# ControllerRC2.net
KiCad netlist of a schematic drawn in EAGLE
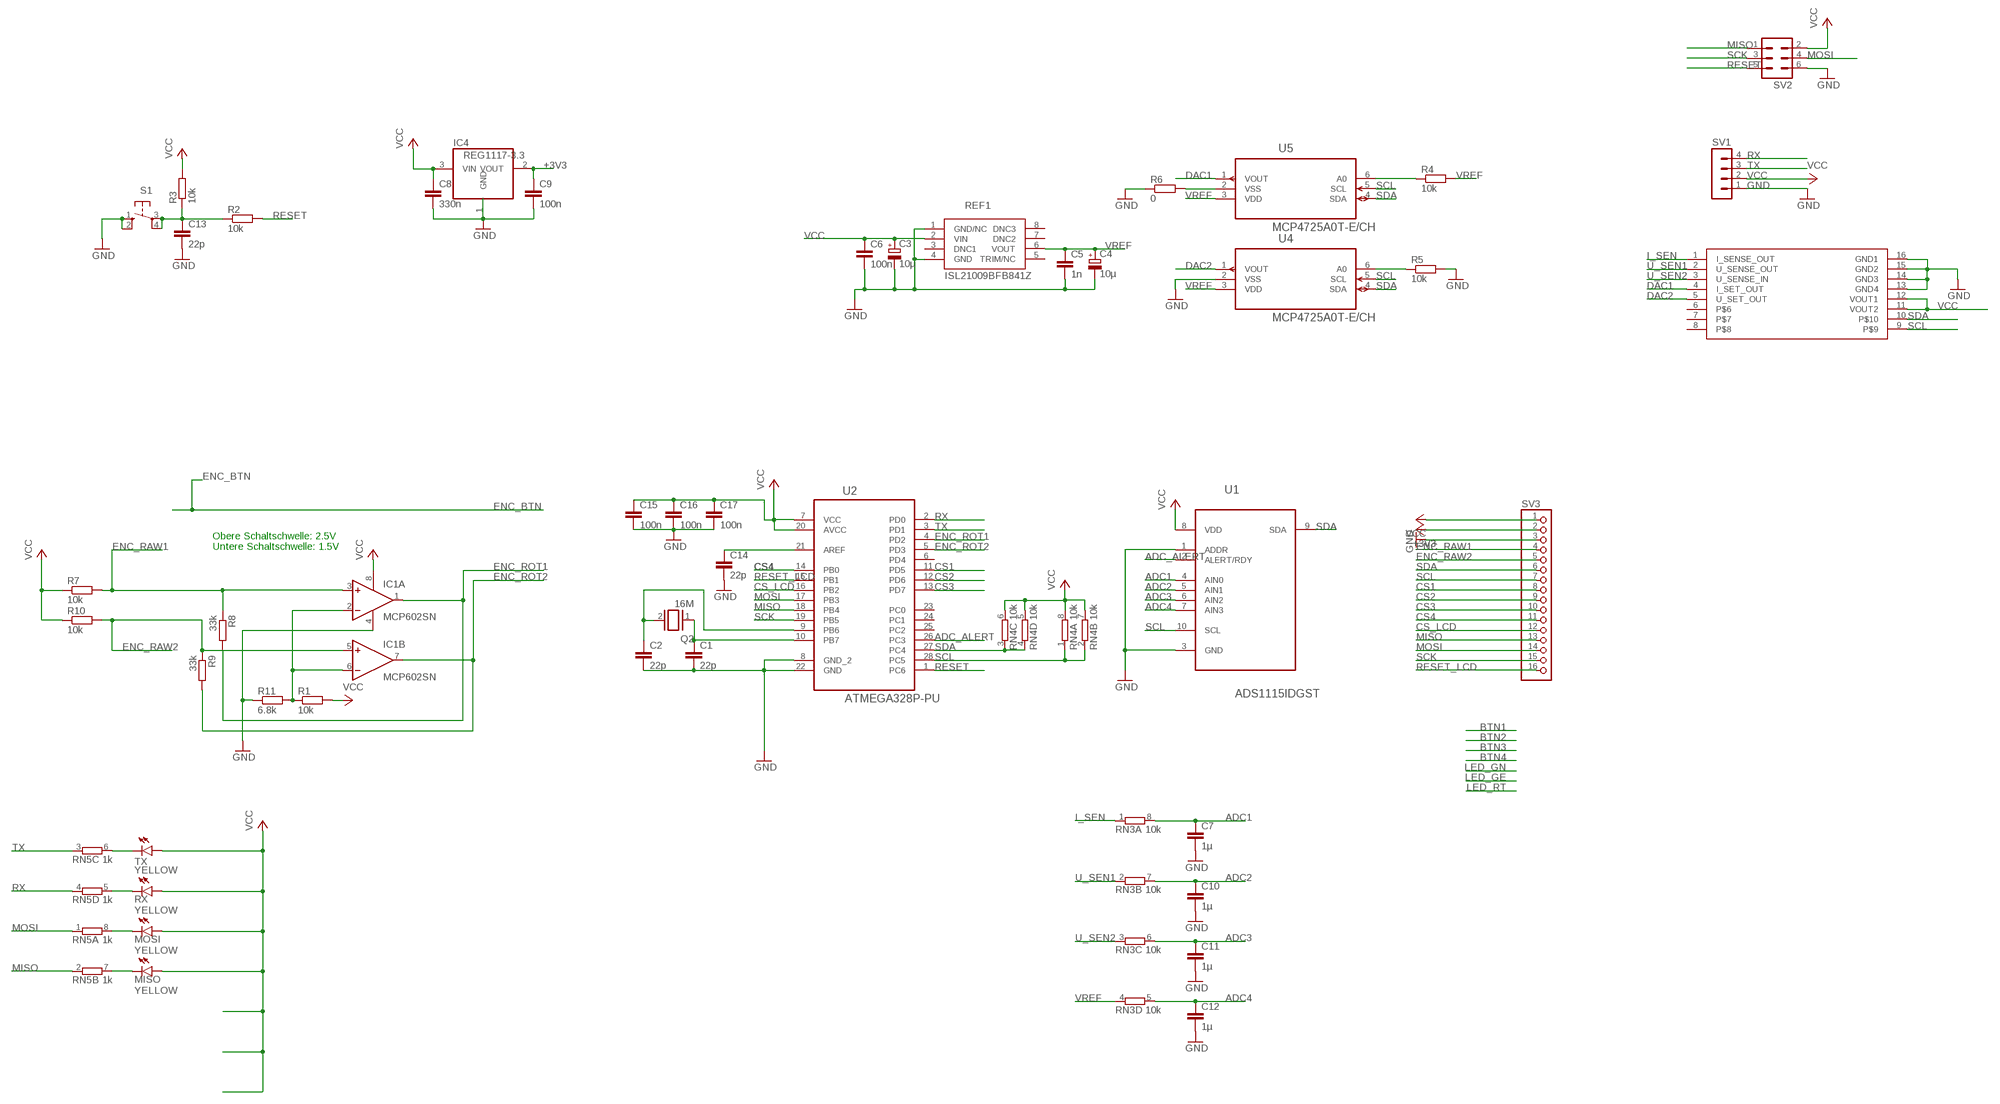
[diagram p0: schematic, sheet 1]

(export (version "E")
  (design (tool "Eeschema 10.0.6"))
  (components
    (comp (ref "C1")
      (value "22p")
      (footprint "eagle-import:C0603")
      (libsource (lib "eagle-import") (part "C-EUC0603"))
    )
    (comp (ref "C2")
      (value "22p")
      (footprint "eagle-import:C0603")
      (libsource (lib "eagle-import") (part "C-EUC0603"))
    )
    (comp (ref "C3")
      (value "10µ")
      (footprint "eagle-import:E2,5-6E")
      (libsource (lib "eagle-import") (part "CPOL-EUE2,5-6E"))
    )
    (comp (ref "C4")
      (value "10µ")
      (footprint "eagle-import:E2,5-6E")
      (libsource (lib "eagle-import") (part "CPOL-EUE2,5-6E"))
    )
    (comp (ref "C5")
      (value "1n")
      (footprint "eagle-import:C0603")
      (libsource (lib "eagle-import") (part "C-EUC0603"))
    )
    (comp (ref "C6")
      (value "100n")
      (footprint "eagle-import:C0603")
      (libsource (lib "eagle-import") (part "C-EUC0603"))
    )
    (comp (ref "C7")
      (value "1µ")
      (footprint "eagle-import:C0603")
      (libsource (lib "eagle-import") (part "C-EUC0603"))
    )
    (comp (ref "C8")
      (value "330n")
      (footprint "eagle-import:C0603")
      (libsource (lib "eagle-import") (part "C-EUC0603"))
    )
    (comp (ref "C9")
      (value "100n")
      (footprint "eagle-import:C0603")
      (libsource (lib "eagle-import") (part "C-EUC0603"))
    )
    (comp (ref "C10")
      (value "1µ")
      (footprint "eagle-import:C0603")
      (libsource (lib "eagle-import") (part "C-EUC0603"))
    )
    (comp (ref "C11")
      (value "1µ")
      (footprint "eagle-import:C0603")
      (libsource (lib "eagle-import") (part "C-EUC0603"))
    )
    (comp (ref "C12")
      (value "1µ")
      (footprint "eagle-import:C0603")
      (libsource (lib "eagle-import") (part "C-EUC0603"))
    )
    (comp (ref "C13")
      (value "22p")
      (footprint "eagle-import:C0603")
      (libsource (lib "eagle-import") (part "C-EUC0603"))
    )
    (comp (ref "C14")
      (value "22p")
      (footprint "eagle-import:C0603")
      (libsource (lib "eagle-import") (part "C-EUC0603"))
    )
    (comp (ref "C15")
      (value "100n")
      (footprint "eagle-import:C0603")
      (libsource (lib "eagle-import") (part "C-EUC0603"))
    )
    (comp (ref "C16")
      (value "100n")
      (footprint "eagle-import:C0603")
      (libsource (lib "eagle-import") (part "C-EUC0603"))
    )
    (comp (ref "C17")
      (value "100n")
      (footprint "eagle-import:C0603")
      (libsource (lib "eagle-import") (part "C-EUC0603"))
    )
    (comp (ref "IC1")
      (value "MCP602SN")
      (footprint "eagle-import:SO08")
      (libsource (lib "eagle-import") (part "MCP602SN"))
    )
    (comp (ref "IC4")
      (value "REG1117-3.3")
      (footprint "eagle-import:SOT223")
      (fields (field (name "MPN") "REG1117"))
      (libsource (lib "eagle-import") (part "REG1117"))
    )
    (comp (ref "MISO")
      (value "YELLOW")
      (footprint "eagle-import:CHIP-LED0805")
      (libsource (lib "eagle-import") (part "LEDCHIP-LED0805"))
    )
    (comp (ref "MOSI")
      (value "YELLOW")
      (footprint "eagle-import:CHIP-LED0805")
      (libsource (lib "eagle-import") (part "LEDCHIP-LED0805"))
    )
    (comp (ref "Q2")
      (value "16M")
      (footprint "eagle-import:QS")
      (libsource (lib "eagle-import") (part "XTAL/S"))
    )
    (comp (ref "R1")
      (value "10k")
      (footprint "eagle-import:R0603")
      (libsource (lib "eagle-import") (part "R-EU_R0603"))
    )
    (comp (ref "R2")
      (value "10k")
      (footprint "eagle-import:R0603")
      (libsource (lib "eagle-import") (part "R-EU_R0603"))
    )
    (comp (ref "R3")
      (value "10k")
      (footprint "eagle-import:R0603")
      (libsource (lib "eagle-import") (part "R-EU_R0603"))
    )
    (comp (ref "R4")
      (value "10k")
      (footprint "eagle-import:R0603")
      (libsource (lib "eagle-import") (part "R-EU_R0603"))
    )
    (comp (ref "R5")
      (value "10k")
      (footprint "eagle-import:R0603")
      (libsource (lib "eagle-import") (part "R-EU_R0603"))
    )
    (comp (ref "R6")
      (value "0")
      (footprint "eagle-import:R0603")
      (libsource (lib "eagle-import") (part "R-EU_R0603"))
    )
    (comp (ref "R7")
      (value "10k")
      (footprint "eagle-import:R0603")
      (libsource (lib "eagle-import") (part "R-EU_R0603"))
    )
    (comp (ref "R8")
      (value "33k")
      (footprint "eagle-import:R0603")
      (libsource (lib "eagle-import") (part "R-EU_R0603"))
    )
    (comp (ref "R9")
      (value "33k")
      (footprint "eagle-import:R0603")
      (libsource (lib "eagle-import") (part "R-EU_R0603"))
    )
    (comp (ref "R10")
      (value "10k")
      (footprint "eagle-import:R0603")
      (libsource (lib "eagle-import") (part "R-EU_R0603"))
    )
    (comp (ref "R11")
      (value "6.8k")
      (footprint "eagle-import:R0603")
      (libsource (lib "eagle-import") (part "R-EU_R0603"))
    )
    (comp (ref "REF1")
      (value "ISL21009BFB841Z")
      (footprint "eagle-import:SOIC127P600X175-8N")
      (libsource (lib "eagle-import") (part "ISL21009BFB841Z"))
    )
    (comp (ref "RN3")
      (value "10k")
      (footprint "eagle-import:0603-ARC")
      (libsource (lib "eagle-import") (part "4R-N0603-ARC"))
    )
    (comp (ref "RN4")
      (value "10k")
      (footprint "eagle-import:0603-ARC")
      (libsource (lib "eagle-import") (part "4R-N0603-ARC"))
    )
    (comp (ref "RN5")
      (value "1k")
      (footprint "eagle-import:0603-ARC")
      (libsource (lib "eagle-import") (part "4R-N0603-ARC"))
    )
    (comp (ref "RX")
      (value "YELLOW")
      (footprint "eagle-import:CHIP-LED0805")
      (libsource (lib "eagle-import") (part "LEDCHIP-LED0805"))
    )
    (comp (ref "S1")
      (value "10-XX")
      (footprint "eagle-import:B3F-10XX")
      (fields (field (name "MPN") "B3F-1000"))
      (libsource (lib "eagle-import") (part "10-XX"))
    )
    (comp (ref "SV1")
      (value "MA04-1")
      (footprint "eagle-import:MA04-1")
      (libsource (lib "eagle-import") (part "MA04-1"))
    )
    (comp (ref "SV2")
      (value "MA03-2")
      (footprint "eagle-import:MA03-2")
      (libsource (lib "eagle-import") (part "MA03-2"))
    )
    (comp (ref "SV3")
      (value "PINHD-1X16")
      (footprint "eagle-import:1X16")
      (libsource (lib "eagle-import") (part "PINHD-1X16"))
    )
    (comp (ref "TX")
      (value "YELLOW")
      (footprint "eagle-import:CHIP-LED0805")
      (libsource (lib "eagle-import") (part "LEDCHIP-LED0805"))
    )
    (comp (ref "U$1")
      (value "DCPINHEADER")
      (footprint "eagle-import:CDIP16")
      (libsource (lib "eagle-import") (part "DCPINHEADER"))
    )
    (comp (ref "U1")
      (value "ADS1115IDGST")
      (footprint "eagle-import:SOP50P490X110-10N")
      (libsource (lib "eagle-import") (part "ADS1115IDGST"))
    )
    (comp (ref "U2")
      (value "ATMEGA328P-PU")
      (footprint "eagle-import:DIP254P762X457-28")
      (libsource (lib "eagle-import") (part "ATMEGA328P-PU"))
    )
    (comp (ref "U4")
      (value "MCP4725A0T-E/CH")
      (footprint "eagle-import:SOT95P270X145-6N")
      (libsource (lib "eagle-import") (part "MCP4725A0T-E/CH"))
    )
    (comp (ref "U5")
      (value "MCP4725A0T-E/CH")
      (footprint "eagle-import:SOT95P270X145-6N")
      (libsource (lib "eagle-import") (part "MCP4725A0T-E/CH"))
    )
  )
  (nets
    (net (code "1") (name "+3V3") (class "Default")
      (node (ref "C9") (pin "1") (pinfunction "1_1") (pintype "passive"))
      (node (ref "IC4") (pin "2") (pinfunction "VOUT_2") (pintype "output"))
      (node (ref "SV3") (pin "2") (pinfunction "2_2") (pintype "passive"))
    )
    (net (code "2") (name "/ADC1") (class "Default")
      (node (ref "C7") (pin "1") (pinfunction "1_1") (pintype "passive"))
      (node (ref "RN3") (pin "8") (pinfunction "2_8") (pintype "passive"))
      (node (ref "U1") (pin "4") (pinfunction "AIN0_4") (pintype "input"))
    )
    (net (code "3") (name "/ADC2") (class "Default")
      (node (ref "C10") (pin "1") (pinfunction "1_1") (pintype "passive"))
      (node (ref "RN3") (pin "7") (pinfunction "2_7") (pintype "passive"))
      (node (ref "U1") (pin "5") (pinfunction "AIN1_5") (pintype "input"))
    )
    (net (code "4") (name "/ADC3") (class "Default")
      (node (ref "C11") (pin "1") (pinfunction "1_1") (pintype "passive"))
      (node (ref "RN3") (pin "6") (pinfunction "2_6") (pintype "passive"))
      (node (ref "U1") (pin "6") (pinfunction "AIN2_6") (pintype "input"))
    )
    (net (code "5") (name "/ADC4") (class "Default")
      (node (ref "C12") (pin "1") (pinfunction "1_1") (pintype "passive"))
      (node (ref "RN3") (pin "5") (pinfunction "2_5") (pintype "passive"))
      (node (ref "U1") (pin "7") (pinfunction "AIN3_7") (pintype "input"))
    )
    (net (code "6") (name "/ADC_ALERT") (class "Default")
      (node (ref "U1") (pin "2") (pinfunction "ALERT/RDY_2") (pintype "input"))
      (node (ref "U2") (pin "26") (pinfunction "PC3_26") (pintype "bidirectional"))
    )
    (net (code "11") (name "/CS1") (class "Default")
      (node (ref "SV3") (pin "8") (pinfunction "8_8") (pintype "passive"))
      (node (ref "U2") (pin "11") (pinfunction "PD5_11") (pintype "bidirectional"))
    )
    (net (code "12") (name "/CS2") (class "Default")
      (node (ref "SV3") (pin "9") (pinfunction "9_9") (pintype "passive"))
      (node (ref "U2") (pin "12") (pinfunction "PD6_12") (pintype "bidirectional"))
    )
    (net (code "13") (name "/CS3") (class "Default")
      (node (ref "SV3") (pin "10") (pinfunction "10_10") (pintype "passive"))
      (node (ref "U2") (pin "13") (pinfunction "PD7_13") (pintype "bidirectional"))
    )
    (net (code "14") (name "/CS4") (class "Default")
      (node (ref "SV3") (pin "11") (pinfunction "11_11") (pintype "passive"))
      (node (ref "U2") (pin "14") (pinfunction "PB0_14") (pintype "bidirectional"))
    )
    (net (code "15") (name "/CS_LCD") (class "Default")
      (node (ref "SV3") (pin "12") (pinfunction "12_12") (pintype "passive"))
      (node (ref "U2") (pin "16") (pinfunction "PB2_16") (pintype "bidirectional"))
    )
    (net (code "16") (name "/DAC1") (class "Default")
      (node (ref "U$1") (pin "4") (pinfunction "I_SET_OUT_4") (pintype "bidirectional"))
      (node (ref "U5") (pin "1") (pinfunction "VOUT_1") (pintype "output"))
    )
    (net (code "17") (name "/DAC2") (class "Default")
      (node (ref "U$1") (pin "5") (pinfunction "U_SET_OUT_5") (pintype "bidirectional"))
      (node (ref "U4") (pin "1") (pinfunction "VOUT_1") (pintype "output"))
    )
    (net (code "19") (name "/ENC_RAW1") (class "Default")
      (node (ref "IC1") (pin "3") (pinfunction "+IN_3") (pintype "input"))
      (node (ref "R7") (pin "2") (pinfunction "2_2") (pintype "passive"))
      (node (ref "R8") (pin "1") (pinfunction "1_1") (pintype "passive"))
      (node (ref "SV3") (pin "4") (pinfunction "4_4") (pintype "passive"))
    )
    (net (code "20") (name "/ENC_RAW2") (class "Default")
      (node (ref "IC1") (pin "5") (pinfunction "+IN_5") (pintype "input"))
      (node (ref "R10") (pin "2") (pinfunction "2_2") (pintype "passive"))
      (node (ref "R9") (pin "1") (pinfunction "1_1") (pintype "passive"))
      (node (ref "SV3") (pin "5") (pinfunction "5_5") (pintype "passive"))
    )
    (net (code "21") (name "/ENC_ROT1") (class "Default")
      (node (ref "IC1") (pin "1") (pinfunction "OUT_1") (pintype "output"))
      (node (ref "R8") (pin "2") (pinfunction "2_2") (pintype "passive"))
      (node (ref "U2") (pin "4") (pinfunction "PD2_4") (pintype "bidirectional"))
    )
    (net (code "22") (name "/ENC_ROT2") (class "Default")
      (node (ref "IC1") (pin "7") (pinfunction "OUT_7") (pintype "output"))
      (node (ref "R9") (pin "2") (pinfunction "2_2") (pintype "passive"))
      (node (ref "U2") (pin "5") (pinfunction "PD3_5") (pintype "bidirectional"))
    )
    (net (code "23") (name "/I_SEN") (class "Default")
      (node (ref "RN3") (pin "1") (pinfunction "1_1") (pintype "passive"))
      (node (ref "U$1") (pin "1") (pinfunction "I_SENSE_OUT_1") (pintype "bidirectional"))
    )
    (net (code "27") (name "/MISO") (class "Default")
      (node (ref "RN5") (pin "2") (pinfunction "1_2") (pintype "passive"))
      (node (ref "SV2") (pin "1") (pinfunction "1_1") (pintype "passive"))
      (node (ref "SV3") (pin "13") (pinfunction "13_13") (pintype "passive"))
      (node (ref "U2") (pin "18") (pinfunction "PB4_18") (pintype "bidirectional"))
    )
    (net (code "28") (name "/MOSI") (class "Default")
      (node (ref "RN5") (pin "1") (pinfunction "1_1") (pintype "passive"))
      (node (ref "SV2") (pin "4") (pinfunction "4_4") (pintype "passive"))
      (node (ref "SV3") (pin "14") (pinfunction "14_14") (pintype "passive"))
      (node (ref "U2") (pin "17") (pinfunction "PB3_17") (pintype "bidirectional"))
    )
    (net (code "29") (name "/RESET") (class "Default")
      (node (ref "R2") (pin "2") (pinfunction "2_2") (pintype "passive"))
      (node (ref "SV2") (pin "5") (pinfunction "5_5") (pintype "passive"))
      (node (ref "U2") (pin "1") (pinfunction "PC6_1") (pintype "bidirectional"))
    )
    (net (code "30") (name "/RESET_LCD") (class "Default")
      (node (ref "SV3") (pin "16") (pinfunction "16_16") (pintype "passive"))
      (node (ref "U2") (pin "15") (pinfunction "PB1_15") (pintype "bidirectional"))
    )
    (net (code "31") (name "/RX") (class "Default")
      (node (ref "RN5") (pin "4") (pinfunction "1_4") (pintype "passive"))
      (node (ref "SV1") (pin "4") (pinfunction "4_4") (pintype "passive"))
      (node (ref "U2") (pin "2") (pinfunction "PD0_2") (pintype "bidirectional"))
    )
    (net (code "32") (name "/SCK") (class "Default")
      (node (ref "SV2") (pin "3") (pinfunction "3_3") (pintype "passive"))
      (node (ref "SV3") (pin "15") (pinfunction "15_15") (pintype "passive"))
      (node (ref "U2") (pin "19") (pinfunction "PB5_19") (pintype "bidirectional"))
    )
    (net (code "33") (name "/SCL") (class "Default")
      (node (ref "RN4") (pin "1") (pinfunction "1_1") (pintype "passive"))
      (node (ref "RN4") (pin "2") (pinfunction "1_2") (pintype "passive"))
      (node (ref "SV3") (pin "7") (pinfunction "7_7") (pintype "passive"))
      (node (ref "U$1") (pin "9") (pinfunction "P$9_9") (pintype "bidirectional"))
      (node (ref "U1") (pin "10") (pinfunction "SCL_10") (pintype "input"))
      (node (ref "U2") (pin "28") (pinfunction "PC5_28") (pintype "bidirectional"))
      (node (ref "U4") (pin "5") (pinfunction "SCL_5") (pintype "input"))
      (node (ref "U5") (pin "5") (pinfunction "SCL_5") (pintype "input"))
    )
    (net (code "34") (name "/SDA") (class "Default")
      (node (ref "RN4") (pin "3") (pinfunction "1_3") (pintype "passive"))
      (node (ref "RN4") (pin "4") (pinfunction "1_4") (pintype "passive"))
      (node (ref "SV3") (pin "6") (pinfunction "6_6") (pintype "passive"))
      (node (ref "U$1") (pin "10") (pinfunction "P$10_10") (pintype "bidirectional"))
      (node (ref "U1") (pin "9") (pinfunction "SDA_9") (pintype "bidirectional"))
      (node (ref "U2") (pin "27") (pinfunction "PC4_27") (pintype "bidirectional"))
      (node (ref "U4") (pin "4") (pinfunction "SDA_4") (pintype "bidirectional"))
      (node (ref "U5") (pin "4") (pinfunction "SDA_4") (pintype "bidirectional"))
    )
    (net (code "35") (name "/TX") (class "Default")
      (node (ref "RN5") (pin "3") (pinfunction "1_3") (pintype "passive"))
      (node (ref "SV1") (pin "3") (pinfunction "3_3") (pintype "passive"))
      (node (ref "U2") (pin "3") (pinfunction "PD1_3") (pintype "bidirectional"))
    )
    (net (code "36") (name "/U_SEN1") (class "Default")
      (node (ref "RN3") (pin "2") (pinfunction "1_2") (pintype "passive"))
      (node (ref "U$1") (pin "2") (pinfunction "U_SENSE_OUT_2") (pintype "bidirectional"))
    )
    (net (code "37") (name "/U_SEN2") (class "Default")
      (node (ref "RN3") (pin "3") (pinfunction "1_3") (pintype "passive"))
      (node (ref "U$1") (pin "3") (pinfunction "U_SENSE_IN_3") (pintype "bidirectional"))
    )
    (net (code "38") (name "/VREF") (class "Default")
      (node (ref "C4") (pin "+") (pinfunction "+_+") (pintype "passive"))
      (node (ref "C5") (pin "1") (pinfunction "1_1") (pintype "passive"))
      (node (ref "R4") (pin "2") (pinfunction "2_2") (pintype "passive"))
      (node (ref "REF1") (pin "6") (pinfunction "VOUT_6") (pintype "bidirectional"))
      (node (ref "RN3") (pin "4") (pinfunction "1_4") (pintype "passive"))
      (node (ref "U4") (pin "3") (pinfunction "VDD_3") (pintype "power_in"))
      (node (ref "U5") (pin "3") (pinfunction "VDD_3") (pintype "power_in"))
    )
    (net (code "39") (name "GND") (class "Default")
      (node (ref "C1") (pin "2") (pinfunction "2_2") (pintype "passive"))
      (node (ref "C10") (pin "2") (pinfunction "2_2") (pintype "passive"))
      (node (ref "C11") (pin "2") (pinfunction "2_2") (pintype "passive"))
      (node (ref "C12") (pin "2") (pinfunction "2_2") (pintype "passive"))
      (node (ref "C13") (pin "2") (pinfunction "2_2") (pintype "passive"))
      (node (ref "C14") (pin "2") (pinfunction "2_2") (pintype "passive"))
      (node (ref "C15") (pin "2") (pinfunction "2_2") (pintype "passive"))
      (node (ref "C16") (pin "2") (pinfunction "2_2") (pintype "passive"))
      (node (ref "C17") (pin "2") (pinfunction "2_2") (pintype "passive"))
      (node (ref "C2") (pin "2") (pinfunction "2_2") (pintype "passive"))
      (node (ref "C3") (pin "-") (pinfunction "-_-") (pintype "passive"))
      (node (ref "C4") (pin "-") (pinfunction "-_-") (pintype "passive"))
      (node (ref "C5") (pin "2") (pinfunction "2_2") (pintype "passive"))
      (node (ref "C6") (pin "2") (pinfunction "2_2") (pintype "passive"))
      (node (ref "C7") (pin "2") (pinfunction "2_2") (pintype "passive"))
      (node (ref "C8") (pin "2") (pinfunction "2_2") (pintype "passive"))
      (node (ref "C9") (pin "2") (pinfunction "2_2") (pintype "passive"))
      (node (ref "IC1") (pin "4") (pinfunction "V-_4") (pintype "power_in"))
      (node (ref "IC4") (pin "1") (pinfunction "GND_1") (pintype "power_in"))
      (node (ref "R11") (pin "1") (pinfunction "1_1") (pintype "passive"))
      (node (ref "R5") (pin "2") (pinfunction "2_2") (pintype "passive"))
      (node (ref "R6") (pin "1") (pinfunction "1_1") (pintype "passive"))
      (node (ref "REF1") (pin "1") (pinfunction "GND/NC_1") (pintype "bidirectional"))
      (node (ref "REF1") (pin "4") (pinfunction "GND_4") (pintype "bidirectional"))
      (node (ref "S1") (pin "1") (pinfunction "S_1") (pintype "passive"))
      (node (ref "S1") (pin "2") (pinfunction "S1_2") (pintype "passive"))
      (node (ref "SV1") (pin "1") (pinfunction "1_1") (pintype "passive"))
      (node (ref "SV2") (pin "6") (pinfunction "6_6") (pintype "passive"))
      (node (ref "SV3") (pin "3") (pinfunction "3_3") (pintype "passive"))
      (node (ref "U$1") (pin "13") (pinfunction "GND4_13") (pintype "bidirectional"))
      (node (ref "U$1") (pin "14") (pinfunction "GND3_14") (pintype "bidirectional"))
      (node (ref "U$1") (pin "15") (pinfunction "GND2_15") (pintype "bidirectional"))
      (node (ref "U$1") (pin "16") (pinfunction "GND1_16") (pintype "bidirectional"))
      (node (ref "U1") (pin "1") (pinfunction "ADDR_1") (pintype "input"))
      (node (ref "U1") (pin "3") (pinfunction "GND_3") (pintype "passive"))
      (node (ref "U2") (pin "22") (pinfunction "GND_22") (pintype "passive"))
      (node (ref "U2") (pin "8") (pinfunction "GND_2_8") (pintype "passive"))
      (node (ref "U4") (pin "2") (pinfunction "VSS_2") (pintype "power_in"))
    )
    (net (code "40") (name "Net-(IC1A--IN)") (class "Default")
      (node (ref "IC1") (pin "2") (pinfunction "-IN_2") (pintype "input"))
      (node (ref "IC1") (pin "6") (pinfunction "-IN_6") (pintype "input"))
      (node (ref "R1") (pin "1") (pinfunction "1_1") (pintype "passive"))
      (node (ref "R11") (pin "2") (pinfunction "2_2") (pintype "passive"))
    )
    (net (code "41") (name "Net-(RN5A-2)") (class "Default")
      (node (ref "MOSI") (pin "C") (pinfunction "C_C") (pintype "passive"))
      (node (ref "RN5") (pin "8") (pinfunction "2_8") (pintype "passive"))
    )
    (net (code "42") (name "Net-(RN5B-2)") (class "Default")
      (node (ref "MISO") (pin "C") (pinfunction "C_C") (pintype "passive"))
      (node (ref "RN5") (pin "7") (pinfunction "2_7") (pintype "passive"))
    )
    (net (code "43") (name "Net-(RN5C-2)") (class "Default")
      (node (ref "RN5") (pin "6") (pinfunction "2_6") (pintype "passive"))
      (node (ref "TX") (pin "C") (pinfunction "C_C") (pintype "passive"))
    )
    (net (code "44") (name "Net-(RN5D-2)") (class "Default")
      (node (ref "RN5") (pin "5") (pinfunction "2_5") (pintype "passive"))
      (node (ref "RX") (pin "C") (pinfunction "C_C") (pintype "passive"))
    )
    (net (code "45") (name "Net-(S1-P)") (class "Default")
      (node (ref "C13") (pin "1") (pinfunction "1_1") (pintype "passive"))
      (node (ref "R2") (pin "1") (pinfunction "1_1") (pintype "passive"))
      (node (ref "R3") (pin "1") (pinfunction "1_1") (pintype "passive"))
      (node (ref "S1") (pin "3") (pinfunction "P_3") (pintype "passive"))
      (node (ref "S1") (pin "4") (pinfunction "P1_4") (pintype "passive"))
    )
    (net (code "46") (name "Net-(U2-AREF)") (class "Default")
      (node (ref "C14") (pin "1") (pinfunction "1_1") (pintype "passive"))
      (node (ref "U2") (pin "21") (pinfunction "AREF_21") (pintype "input"))
    )
    (net (code "47") (name "Net-(U2-PB6)") (class "Default")
      (node (ref "C2") (pin "1") (pinfunction "1_1") (pintype "passive"))
      (node (ref "Q2") (pin "2") (pinfunction "2_2") (pintype "passive"))
      (node (ref "U2") (pin "9") (pinfunction "PB6_9") (pintype "bidirectional"))
    )
    (net (code "48") (name "Net-(U2-PB7)") (class "Default")
      (node (ref "C1") (pin "1") (pinfunction "1_1") (pintype "passive"))
      (node (ref "Q2") (pin "1") (pinfunction "1_1") (pintype "passive"))
      (node (ref "U2") (pin "10") (pinfunction "PB7_10") (pintype "bidirectional"))
    )
    (net (code "49") (name "Net-(U4-A0)") (class "Default")
      (node (ref "R5") (pin "1") (pinfunction "1_1") (pintype "passive"))
      (node (ref "U4") (pin "6") (pinfunction "A0_6") (pintype "passive"))
    )
    (net (code "50") (name "Net-(U5-A0)") (class "Default")
      (node (ref "R4") (pin "1") (pinfunction "1_1") (pintype "passive"))
      (node (ref "U5") (pin "6") (pinfunction "A0_6") (pintype "passive"))
    )
    (net (code "51") (name "Net-(U5-VSS)") (class "Default")
      (node (ref "R6") (pin "2") (pinfunction "2_2") (pintype "passive"))
      (node (ref "U5") (pin "2") (pinfunction "VSS_2") (pintype "power_in"))
    )
    (net (code "52") (name "VCC") (class "Default")
      (node (ref "C15") (pin "1") (pinfunction "1_1") (pintype "passive"))
      (node (ref "C16") (pin "1") (pinfunction "1_1") (pintype "passive"))
      (node (ref "C17") (pin "1") (pinfunction "1_1") (pintype "passive"))
      (node (ref "C3") (pin "+") (pinfunction "+_+") (pintype "passive"))
      (node (ref "C6") (pin "1") (pinfunction "1_1") (pintype "passive"))
      (node (ref "C8") (pin "1") (pinfunction "1_1") (pintype "passive"))
      (node (ref "IC1") (pin "8") (pinfunction "V+_8") (pintype "power_in"))
      (node (ref "IC4") (pin "3") (pinfunction "VIN_3") (pintype "input"))
      (node (ref "MISO") (pin "A") (pinfunction "A_A") (pintype "passive"))
      (node (ref "MOSI") (pin "A") (pinfunction "A_A") (pintype "passive"))
      (node (ref "R1") (pin "2") (pinfunction "2_2") (pintype "passive"))
      (node (ref "R10") (pin "1") (pinfunction "1_1") (pintype "passive"))
      (node (ref "R3") (pin "2") (pinfunction "2_2") (pintype "passive"))
      (node (ref "R7") (pin "1") (pinfunction "1_1") (pintype "passive"))
      (node (ref "REF1") (pin "2") (pinfunction "VIN_2") (pintype "bidirectional"))
      (node (ref "RN4") (pin "5") (pinfunction "2_5") (pintype "passive"))
      (node (ref "RN4") (pin "6") (pinfunction "2_6") (pintype "passive"))
      (node (ref "RN4") (pin "7") (pinfunction "2_7") (pintype "passive"))
      (node (ref "RN4") (pin "8") (pinfunction "2_8") (pintype "passive"))
      (node (ref "RX") (pin "A") (pinfunction "A_A") (pintype "passive"))
      (node (ref "SV1") (pin "2") (pinfunction "2_2") (pintype "passive"))
      (node (ref "SV2") (pin "2") (pinfunction "2_2") (pintype "passive"))
      (node (ref "SV3") (pin "1") (pinfunction "1_1") (pintype "passive"))
      (node (ref "TX") (pin "A") (pinfunction "A_A") (pintype "passive"))
      (node (ref "U$1") (pin "11") (pinfunction "VOUT2_11") (pintype "bidirectional"))
      (node (ref "U$1") (pin "12") (pinfunction "VOUT1_12") (pintype "bidirectional"))
      (node (ref "U1") (pin "8") (pinfunction "VDD_8") (pintype "power_in"))
      (node (ref "U2") (pin "20") (pinfunction "AVCC_20") (pintype "power_in"))
      (node (ref "U2") (pin "7") (pinfunction "VCC_7") (pintype "power_in"))
    )
    (net (code "53") (name "unconnected-(REF1-DNC1-Pad3)") (class "Default")
      (node (ref "REF1") (pin "3") (pinfunction "DNC1_3") (pintype "bidirectional"))
    )
    (net (code "54") (name "unconnected-(REF1-DNC2-Pad7)") (class "Default")
      (node (ref "REF1") (pin "7") (pinfunction "DNC2_7") (pintype "bidirectional"))
    )
    (net (code "55") (name "unconnected-(REF1-DNC3-Pad8)") (class "Default")
      (node (ref "REF1") (pin "8") (pinfunction "DNC3_8") (pintype "bidirectional"))
    )
    (net (code "56") (name "unconnected-(REF1-TRIM{slash}NC-Pad5)") (class "Default")
      (node (ref "REF1") (pin "5") (pinfunction "TRIM/NC_5") (pintype "bidirectional"))
    )
    (net (code "57") (name "unconnected-(U$1-P$6-Pad6)") (class "Default")
      (node (ref "U$1") (pin "6") (pinfunction "P$6_6") (pintype "bidirectional"))
    )
    (net (code "58") (name "unconnected-(U$1-P$7-Pad7)") (class "Default")
      (node (ref "U$1") (pin "7") (pinfunction "P$7_7") (pintype "bidirectional"))
    )
    (net (code "59") (name "unconnected-(U$1-P$8-Pad8)") (class "Default")
      (node (ref "U$1") (pin "8") (pinfunction "P$8_8") (pintype "bidirectional"))
    )
    (net (code "60") (name "unconnected-(U2-PC0-Pad23)") (class "Default")
      (node (ref "U2") (pin "23") (pinfunction "PC0_23") (pintype "bidirectional"))
    )
    (net (code "61") (name "unconnected-(U2-PC1-Pad24)") (class "Default")
      (node (ref "U2") (pin "24") (pinfunction "PC1_24") (pintype "bidirectional"))
    )
    (net (code "62") (name "unconnected-(U2-PC2-Pad25)") (class "Default")
      (node (ref "U2") (pin "25") (pinfunction "PC2_25") (pintype "bidirectional"))
    )
    (net (code "63") (name "unconnected-(U2-PD4-Pad6)") (class "Default")
      (node (ref "U2") (pin "6") (pinfunction "PD4_6") (pintype "bidirectional"))
    )
  )
)
